# LCD.net
KiCad netlist of a schematic drawn in Altium Designer
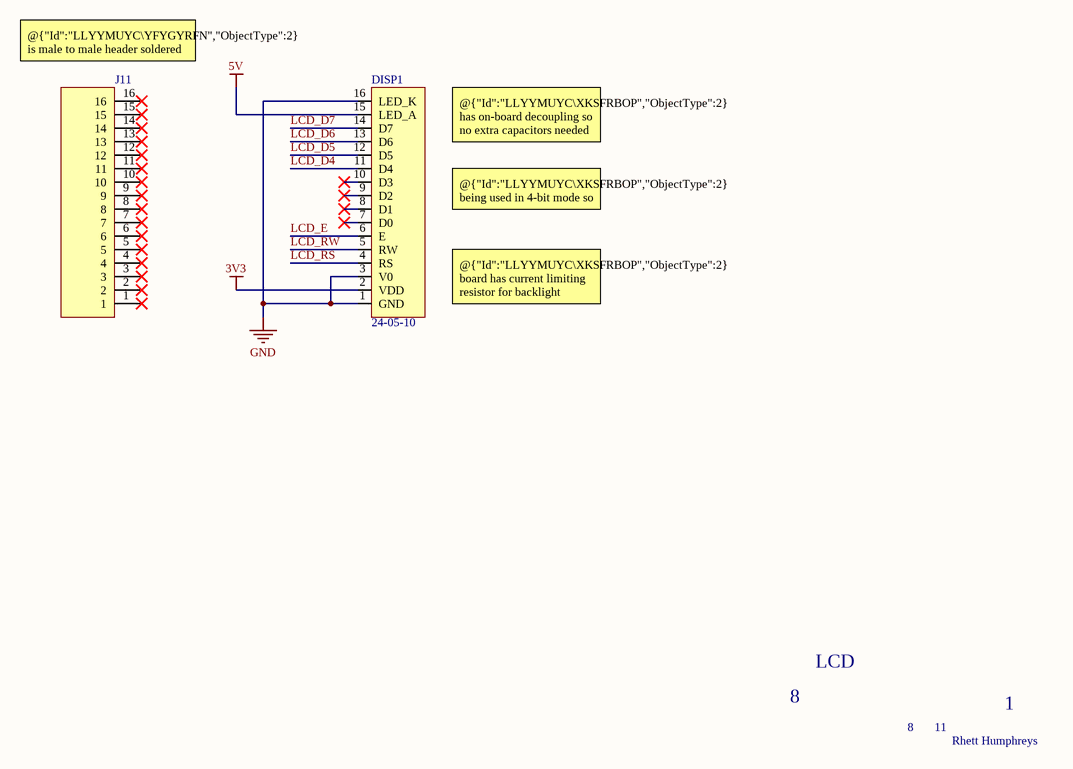
[diagram p0: LCD.SchDoc]

(export (version "E")
  (design (tool "Eeschema 10.0.6"))
  (components
    (comp (ref "DISP1")
      (value "24-05-10")
      (footprint "ERM2004 40x2 LCD")
      (libsource (lib "Master") (part "ERM2004 40x2 LCD"))
    )
    (comp (ref "J11") (value "Header, 16pos 2.54mm") (libsource (lib "Master") (part "Header, 16pos 2.54mm")))
  )
  (nets
    (net (code "1") (name "/LCD_D4") (class "Default")
      (node (ref "DISP1") (pin "11") (pinfunction "D4_11") (pintype "passive"))
    )
    (net (code "2") (name "/LCD_D5") (class "Default")
      (node (ref "DISP1") (pin "12") (pinfunction "D5_12") (pintype "passive"))
    )
    (net (code "3") (name "/LCD_D6") (class "Default")
      (node (ref "DISP1") (pin "13") (pinfunction "D6_13") (pintype "passive"))
    )
    (net (code "4") (name "/LCD_D7") (class "Default")
      (node (ref "DISP1") (pin "14") (pinfunction "D7_14") (pintype "passive"))
    )
    (net (code "5") (name "/LCD_E") (class "Default")
      (node (ref "DISP1") (pin "6") (pinfunction "E_6") (pintype "passive"))
    )
    (net (code "6") (name "/LCD_RS") (class "Default")
      (node (ref "DISP1") (pin "4") (pinfunction "RS_4") (pintype "passive"))
    )
    (net (code "7") (name "/LCD_RW") (class "Default")
      (node (ref "DISP1") (pin "5") (pinfunction "RW_5") (pintype "passive"))
    )
    (net (code "8") (name "3V3") (class "Default")
      (node (ref "DISP1") (pin "2") (pinfunction "VDD_2") (pintype "passive"))
    )
    (net (code "9") (name "5V") (class "Default")
      (node (ref "DISP1") (pin "15") (pinfunction "LED_A_15") (pintype "passive"))
    )
    (net (code "10") (name "GND") (class "Default")
      (node (ref "DISP1") (pin "1") (pinfunction "GND_1") (pintype "passive"))
      (node (ref "DISP1") (pin "16") (pinfunction "LED_K_16") (pintype "passive"))
      (node (ref "DISP1") (pin "3") (pinfunction "V0_3") (pintype "passive"))
    )
    (net (code "11") (name "unconnected-(DISP1-D0-Pad7)") (class "Default")
      (node (ref "DISP1") (pin "7") (pinfunction "D0_7") (pintype "passive+no_connect"))
    )
    (net (code "12") (name "unconnected-(DISP1-D1-Pad8)") (class "Default")
      (node (ref "DISP1") (pin "8") (pinfunction "D1_8") (pintype "passive+no_connect"))
    )
    (net (code "13") (name "unconnected-(DISP1-D2-Pad9)") (class "Default")
      (node (ref "DISP1") (pin "9") (pinfunction "D2_9") (pintype "passive+no_connect"))
    )
    (net (code "14") (name "unconnected-(DISP1-D3-Pad10)") (class "Default")
      (node (ref "DISP1") (pin "10") (pinfunction "D3_10") (pintype "passive+no_connect"))
    )
    (net (code "15") (name "unconnected-(J11-Pad1)") (class "Default")
      (node (ref "J11") (pin "1") (pinfunction "1_1") (pintype "passive+no_connect"))
    )
    (net (code "16") (name "unconnected-(J11-Pad2)") (class "Default")
      (node (ref "J11") (pin "2") (pinfunction "2_2") (pintype "passive+no_connect"))
    )
    (net (code "17") (name "unconnected-(J11-Pad3)") (class "Default")
      (node (ref "J11") (pin "3") (pinfunction "3_3") (pintype "passive+no_connect"))
    )
    (net (code "18") (name "unconnected-(J11-Pad4)") (class "Default")
      (node (ref "J11") (pin "4") (pinfunction "4_4") (pintype "passive+no_connect"))
    )
    (net (code "19") (name "unconnected-(J11-Pad5)") (class "Default")
      (node (ref "J11") (pin "5") (pinfunction "5_5") (pintype "passive+no_connect"))
    )
    (net (code "20") (name "unconnected-(J11-Pad6)") (class "Default")
      (node (ref "J11") (pin "6") (pinfunction "6_6") (pintype "passive+no_connect"))
    )
    (net (code "21") (name "unconnected-(J11-Pad7)") (class "Default")
      (node (ref "J11") (pin "7") (pinfunction "7_7") (pintype "passive+no_connect"))
    )
    (net (code "22") (name "unconnected-(J11-Pad8)") (class "Default")
      (node (ref "J11") (pin "8") (pinfunction "8_8") (pintype "passive+no_connect"))
    )
    (net (code "23") (name "unconnected-(J11-Pad9)") (class "Default")
      (node (ref "J11") (pin "9") (pinfunction "9_9") (pintype "passive+no_connect"))
    )
    (net (code "24") (name "unconnected-(J11-Pad10)") (class "Default")
      (node (ref "J11") (pin "10") (pinfunction "10_10") (pintype "passive+no_connect"))
    )
    (net (code "25") (name "unconnected-(J11-Pad11)") (class "Default")
      (node (ref "J11") (pin "11") (pinfunction "11_11") (pintype "passive+no_connect"))
    )
    (net (code "26") (name "unconnected-(J11-Pad12)") (class "Default")
      (node (ref "J11") (pin "12") (pinfunction "12_12") (pintype "passive+no_connect"))
    )
    (net (code "27") (name "unconnected-(J11-Pad13)") (class "Default")
      (node (ref "J11") (pin "13") (pinfunction "13_13") (pintype "passive+no_connect"))
    )
    (net (code "28") (name "unconnected-(J11-Pad14)") (class "Default")
      (node (ref "J11") (pin "14") (pinfunction "14_14") (pintype "passive+no_connect"))
    )
    (net (code "29") (name "unconnected-(J11-Pad15)") (class "Default")
      (node (ref "J11") (pin "15") (pinfunction "15_15") (pintype "passive+no_connect"))
    )
    (net (code "30") (name "unconnected-(J11-Pad16)") (class "Default")
      (node (ref "J11") (pin "16") (pinfunction "16_16") (pintype "passive+no_connect"))
    )
  )
)
